# UNO-TH_Rev3e.net
KiCad netlist of a schematic drawn in Altium Designer
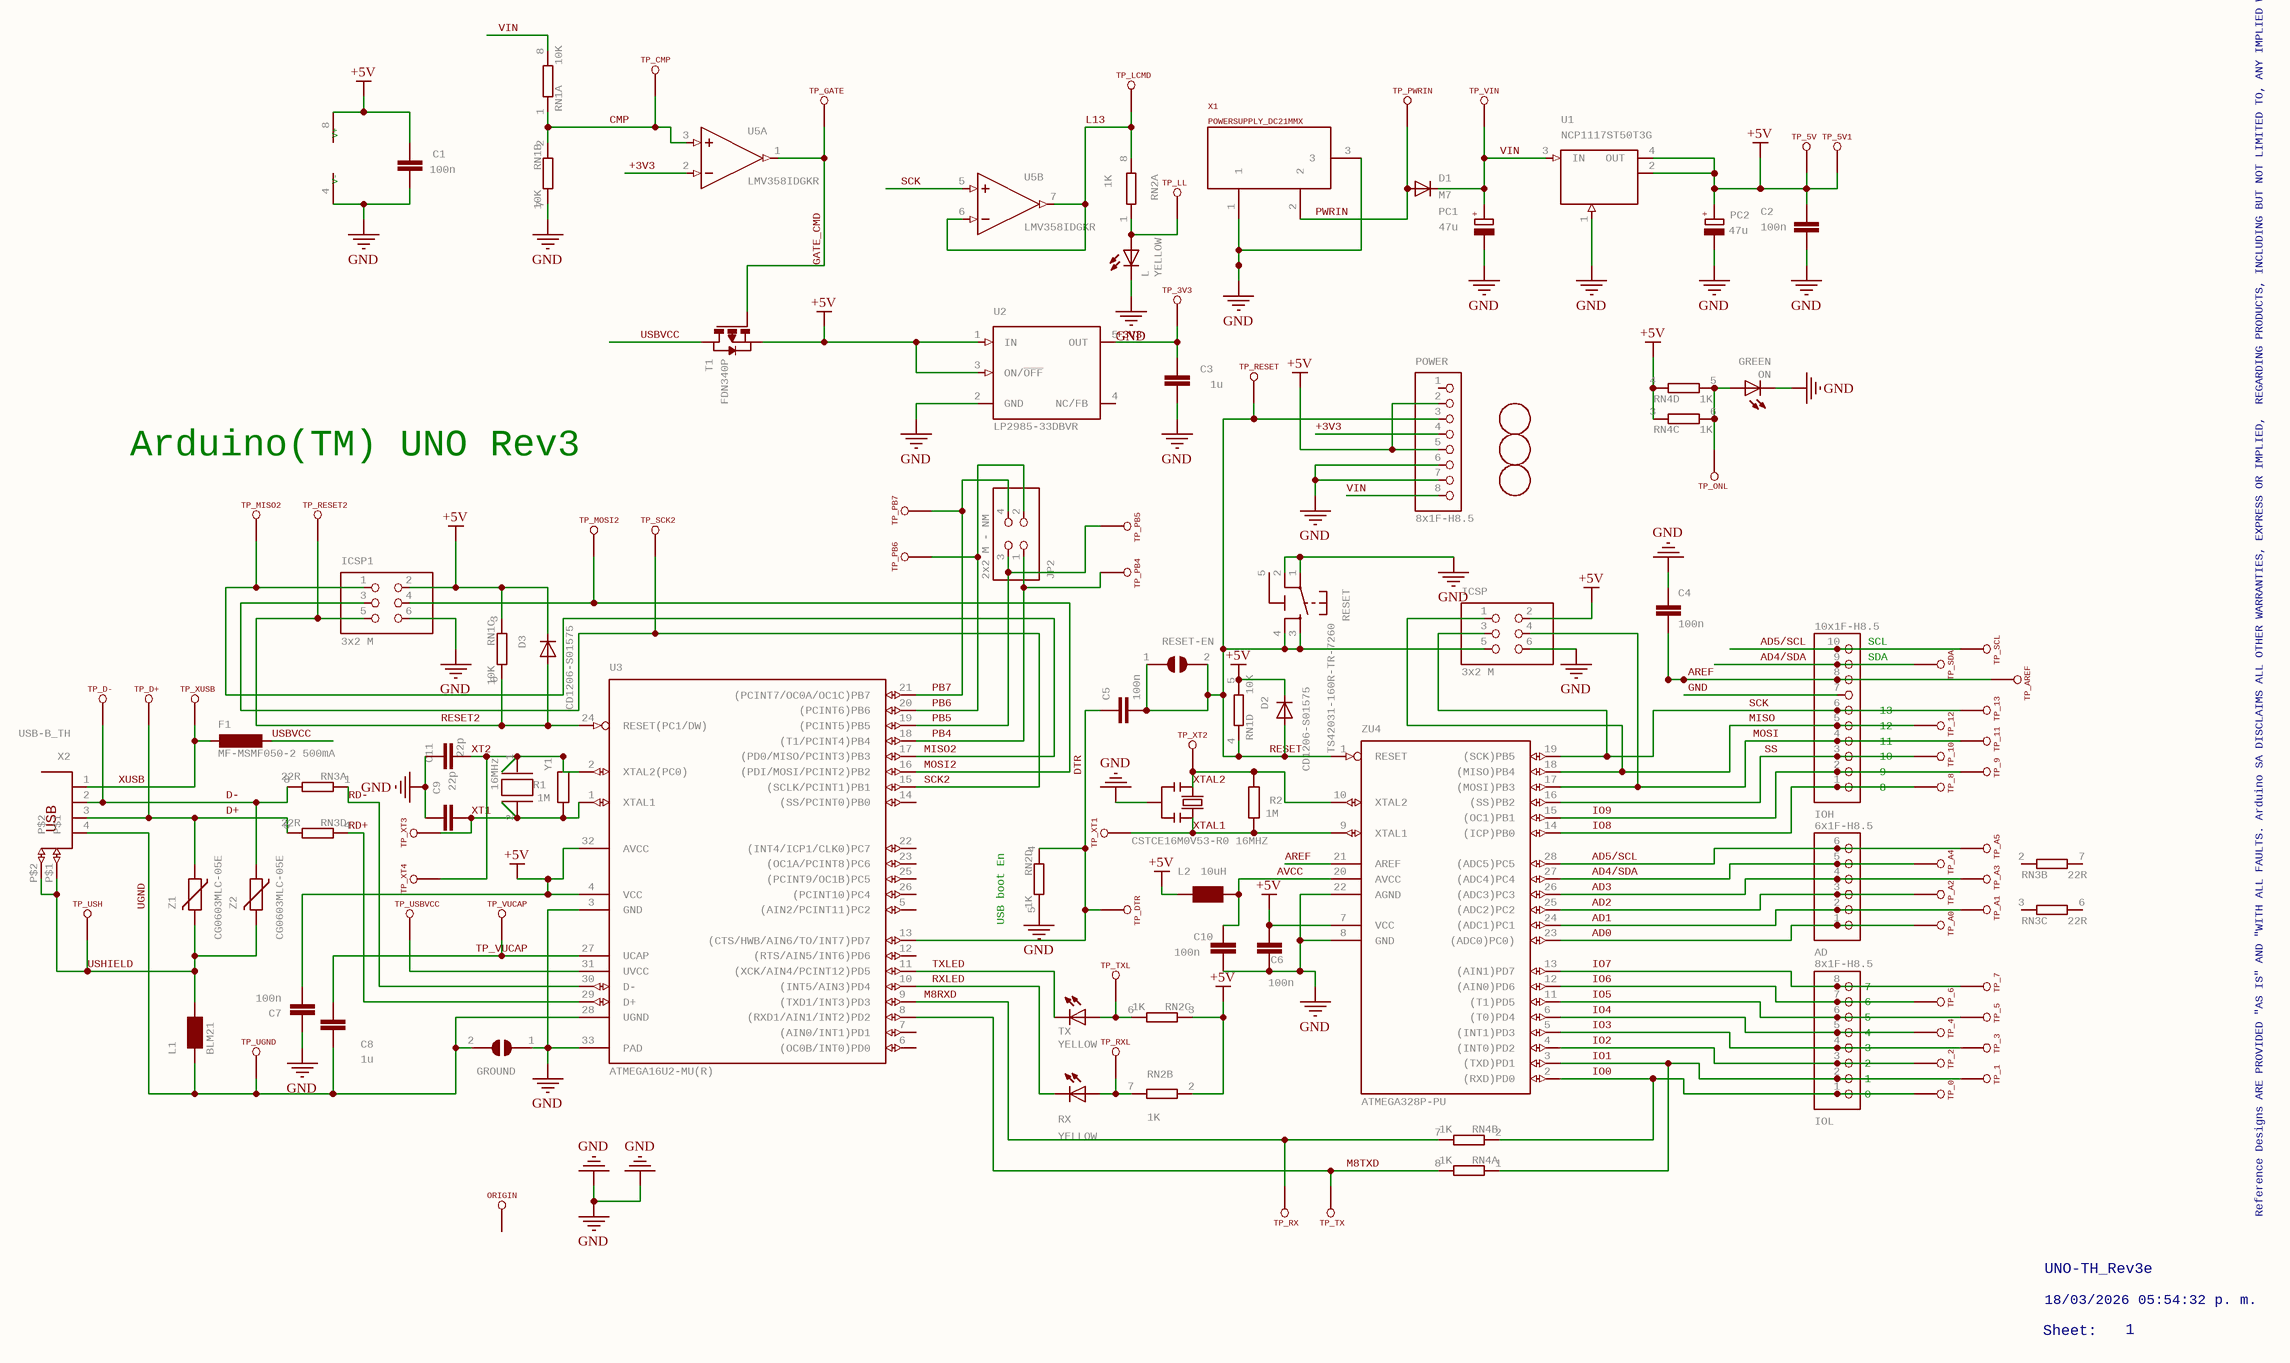
[diagram p0: UNO-TH_Rev3e.SchDoc]

(export (version "E")
  (design (tool "Eeschema 10.0.6"))
  (components
    (comp (ref "AD")
      (value "6x1F-H8.5")
      (footprint "1X06")
      (description "PIN HEADER")
      (libsource (lib "SmartPrj") (part "PINHD-1X6"))
    )
    (comp (ref "C1")
      (value "100n")
      (footprint "C0603-ROUND")
      (description "CAPACITOR, European symbol")
      (libsource (lib "") (part "C-EU0603-RND_1"))
    )
    (comp (ref "C2")
      (value "100n")
      (footprint "C0603-ROUND")
      (description "CAPACITOR, European symbol")
      (libsource (lib "SmartPrj") (part "C-EU0603-RND"))
    )
    (comp (ref "C3")
      (value "1u")
      (footprint "C0603-ROUND")
      (description "CAPACITOR, European symbol")
      (libsource (lib "") (part "C-EU0603-RND_1"))
    )
    (comp (ref "C4")
      (value "100n")
      (footprint "C0603-ROUND")
      (description "CAPACITOR, European symbol")
      (libsource (lib "") (part "C-EU0603-RND_2"))
    )
    (comp (ref "C5")
      (value "100n")
      (footprint "C0603-ROUND")
      (description "CAPACITOR, European symbol")
      (libsource (lib "") (part "C-EU0603-RND_1"))
    )
    (comp (ref "C6")
      (value "100n")
      (footprint "C0603-ROUND")
      (description "CAPACITOR, European symbol")
      (libsource (lib "SmartPrj") (part "C-EU0603-RND"))
    )
    (comp (ref "C7")
      (value "100n")
      (footprint "C0603-ROUND")
      (description "CAPACITOR, European symbol")
      (libsource (lib "") (part "C-EU0603-RND_3"))
    )
    (comp (ref "C8")
      (value "1u")
      (footprint "C0603-ROUND")
      (description "CAPACITOR, European symbol")
      (libsource (lib "") (part "C-EU0603-RND_3"))
    )
    (comp (ref "C9")
      (value "22p")
      (footprint "C0603-ROUND")
      (description "CAPACITOR, European symbol")
      (libsource (lib "") (part "C-EU0603-RND_2"))
    )
    (comp (ref "C10")
      (value "100n")
      (footprint "C0603-ROUND")
      (description "CAPACITOR, European symbol")
      (libsource (lib "SmartPrj") (part "C-EU0603-RND"))
    )
    (comp (ref "C11")
      (value "22p")
      (footprint "C0603-ROUND")
      (description "CAPACITOR, European symbol")
      (libsource (lib "") (part "C-EU0603-RND_2"))
    )
    (comp (ref "D1")
      (value "M7")
      (footprint "SMB")
      (description "DIODE")
      (libsource (lib "diode") (part "DIODE-SMB"))
    )
    (comp (ref "D2")
      (value "CD1206-S01575")
      (footprint "MINIMELF")
      (description "DIODE")
      (libsource (lib "diode") (part "DIODE-MINIMELF"))
    )
    (comp (ref "D3")
      (value "CD1206-S01575")
      (footprint "MINIMELF")
      (description "DIODE")
      (libsource (lib "diode") (part "DIODE-MINIMELF"))
    )
    (comp (ref "F1")
      (value "MF-MSMF050-2 500mA")
      (footprint "L1812")
      (description "INDUCTOR, European symbol")
      (libsource (lib "rcl") (part "L-EUL1812"))
    )
    (comp (ref "FD1")
      (value "FIDUCIALMOUNT")
      (footprint "FIDUCIA-MOUNT")
      (libsource (lib "SmartPrj") (part "FIDUCIALMOUNT"))
    )
    (comp (ref "FD2")
      (value "FIDUCIALMOUNT")
      (footprint "FIDUCIA-MOUNT")
      (libsource (lib "SmartPrj") (part "FIDUCIALMOUNT"))
    )
    (comp (ref "FD3")
      (value "FIDUCIALMOUNT")
      (footprint "FIDUCIA-MOUNT")
      (libsource (lib "SmartPrj") (part "FIDUCIALMOUNT"))
    )
    (comp (ref "GROUND")
      (value "SJ")
      (footprint "SJ")
      (description "SMD solder JUMPER")
      (libsource (lib "jumper") (part "SJ"))
    )
    (comp (ref "ICSP")
      (value "3x2 M")
      (footprint "2X03")
      (description "PIN HEADER")
      (libsource (lib "SmartPrj") (part "PINHD-2X3"))
    )
    (comp (ref "ICSP1")
      (value "3x2 M")
      (footprint "2X03")
      (description "PIN HEADER")
      (libsource (lib "SmartPrj") (part "PINHD-2X3"))
    )
    (comp (ref "IOH")
      (value "10x1F-H8.5")
      (footprint "1X10")
      (description "PIN HEADER")
      (libsource (lib "SmartPrj") (part "PINHD-1X10_ARD"))
    )
    (comp (ref "IOL")
      (value "8x1F-H8.5")
      (footprint "1X08")
      (description "PIN HEADER")
      (libsource (lib "SmartPrj") (part "PINHD-1X8"))
    )
    (comp (ref "JP2")
      (value "2x2 M - NM")
      (footprint "2X02")
      (description "PIN HEADER")
      (libsource (lib "SmartPrj") (part "PINHD-2X2"))
    )
    (comp (ref "L")
      (value "YELLOW")
      (footprint "CHIP-LED0805")
      (libsource (lib "led") (part "LEDCHIP-LED0805"))
    )
    (comp (ref "L1")
      (value "BLM21")
      (footprint "0805")
      (libsource (lib "wuerth-elektronik") (part "WE-CBF_0805"))
    )
    (comp (ref "L2")
      (value "10uH")
      (footprint "0805")
      (description "10uH 0805")
      (fields (field (name "PART_NUMBER") "CV201210-100K"))
      (libsource (lib "Induttanze") (part "0715_CV201210-100K"))
    )
    (comp (ref "ON")
      (value "GREEN")
      (footprint "CHIP-LED0805")
      (libsource (lib "led") (part "LEDCHIP-LED0805"))
    )
    (comp (ref "ORIGIN") (value "TP_SP") (footprint "TP-SP") (libsource (lib "SmartPrj") (part "TP_SP")))
    (comp (ref "PC1")
      (value "47u")
      (footprint "PANASONIC_D")
      (description "POLARIZED CAPACITOR, European symbol")
      (fields (field (name "+") "+"))
      (libsource (lib "rcl") (part "CPOL-EUD"))
    )
    (comp (ref "PC2")
      (value "47u")
      (footprint "PANASONIC_D")
      (description "POLARIZED CAPACITOR, European symbol")
      (fields (field (name "+") "+"))
      (libsource (lib "rcl") (part "CPOL-EUD"))
    )
    (comp (ref "POWER")
      (value "8x1F-H8.5")
      (footprint "1X08")
      (description "PIN HEADER")
      (libsource (lib "SmartPrj") (part "PINHD-1X8"))
    )
    (comp (ref "R1")
      (value "1M")
      (footprint "R0603-ROUND")
      (description "RESISTOR, European symbol")
      (libsource (lib "SmartPrj") (part "R-EU_R0603"))
    )
    (comp (ref "R2")
      (value "1M")
      (footprint "R0603-ROUND")
      (description "RESISTOR, European symbol")
      (libsource (lib "SmartPrj") (part "R-EU_R0603"))
    )
    (comp (ref "RESET")
      (value "TS42031-160R-TR-7260")
      (footprint "TS42")
      (description "TS42 Dongnan Electronics Tact switch VDC 12V - 50mA")
      (libsource (lib "SmartPrj") (part "TS42"))
    )
    (comp (ref "RESET-EN")
      (value "SJ")
      (footprint "SJ")
      (description "SMD solder JUMPER")
      (libsource (lib "jumper") (part "SJ"))
    )
    (comp (ref "RN1")
      (value "10K")
      (footprint "CAY16")
      (description "Array Chip Resistor   Source: RS Component / Phycomp")
      (libsource (lib "resistor-dil") (part "4R-NCAY16"))
    )
    (comp (ref "RN2")
      (value "1K")
      (footprint "CAY16")
      (description "Array Chip Resistor   Source: RS Component / Phycomp")
      (libsource (lib "resistor-dil") (part "4R-NCAY16"))
    )
    (comp (ref "RN3")
      (value "22R")
      (footprint "CAY16")
      (description "Array Chip Resistor   Source: RS Component / Phycomp")
      (libsource (lib "resistor-dil") (part "4R-NCAY16"))
    )
    (comp (ref "RN4")
      (value "1K")
      (footprint "CAY16")
      (description "Array Chip Resistor   Source: RS Component / Phycomp")
      (libsource (lib "resistor-dil") (part "4R-NCAY16"))
    )
    (comp (ref "RX")
      (value "YELLOW")
      (footprint "CHIP-LED0805")
      (libsource (lib "led") (part "LEDCHIP-LED0805"))
    )
    (comp (ref "T1")
      (value "FDN340P")
      (footprint "SOT-23")
      (description "MOS FET")
      (libsource (lib "zetex") (part "PMOSSOT23"))
    )
    (comp (ref "TP_0") (value "TP_SP") (footprint "TP-SP") (libsource (lib "SmartPrj") (part "TP_SP")))
    (comp (ref "TP_1") (value "TP_SP") (footprint "TP-SP") (libsource (lib "SmartPrj") (part "TP_SP")))
    (comp (ref "TP_2") (value "TP_SP") (footprint "TP-SP") (libsource (lib "SmartPrj") (part "TP_SP")))
    (comp (ref "TP_3") (value "TP_SP") (footprint "TP-SP") (libsource (lib "SmartPrj") (part "TP_SP")))
    (comp (ref "TP_3V3") (value "TP_SP") (footprint "TP-SP") (libsource (lib "SmartPrj") (part "TP_SP")))
    (comp (ref "TP_4") (value "TP_SP") (footprint "TP-SP") (libsource (lib "SmartPrj") (part "TP_SP")))
    (comp (ref "TP_5") (value "TP_SP") (footprint "TP-SP") (libsource (lib "SmartPrj") (part "TP_SP")))
    (comp (ref "TP_5V") (value "TP_SP") (footprint "TP-SP") (libsource (lib "SmartPrj") (part "TP_SP")))
    (comp (ref "TP_5V1") (value "TP_SP") (footprint "TP-SP") (libsource (lib "SmartPrj") (part "TP_SP")))
    (comp (ref "TP_6") (value "TP_SP") (footprint "TP-SP") (libsource (lib "SmartPrj") (part "TP_SP")))
    (comp (ref "TP_7") (value "TP_SP") (footprint "TP-SP") (libsource (lib "SmartPrj") (part "TP_SP")))
    (comp (ref "TP_8") (value "TP_SP") (footprint "TP-SP") (libsource (lib "SmartPrj") (part "TP_SP")))
    (comp (ref "TP_9") (value "TP_SP") (footprint "TP-SP") (libsource (lib "SmartPrj") (part "TP_SP")))
    (comp (ref "TP_10") (value "TP_SP") (footprint "TP-SP") (libsource (lib "SmartPrj") (part "TP_SP")))
    (comp (ref "TP_11") (value "TP_SP") (footprint "TP-SP") (libsource (lib "SmartPrj") (part "TP_SP")))
    (comp (ref "TP_12") (value "TP_SP") (footprint "TP-SP") (libsource (lib "SmartPrj") (part "TP_SP")))
    (comp (ref "TP_13") (value "TP_SP") (footprint "TP-SP") (libsource (lib "SmartPrj") (part "TP_SP")))
    (comp (ref "TP_A0") (value "TP_SP") (footprint "TP-SP") (libsource (lib "SmartPrj") (part "TP_SP")))
    (comp (ref "TP_A1") (value "TP_SP") (footprint "TP-SP") (libsource (lib "SmartPrj") (part "TP_SP")))
    (comp (ref "TP_A2") (value "TP_SP") (footprint "TP-SP") (libsource (lib "SmartPrj") (part "TP_SP")))
    (comp (ref "TP_A3") (value "TP_SP") (footprint "TP-SP") (libsource (lib "SmartPrj") (part "TP_SP")))
    (comp (ref "TP_A4") (value "TP_SP") (footprint "TP-SP") (libsource (lib "SmartPrj") (part "TP_SP")))
    (comp (ref "TP_A5") (value "TP_SP") (footprint "TP-SP") (libsource (lib "SmartPrj") (part "TP_SP")))
    (comp (ref "TP_AREF") (value "TP_SP") (footprint "TP-SP") (libsource (lib "SmartPrj") (part "TP_SP")))
    (comp (ref "TP_CMP") (value "TP_SP") (footprint "TP-SP") (libsource (lib "SmartPrj") (part "TP_SP")))
    (comp (ref "TP_D+") (value "TP_SP") (footprint "TP-SP") (libsource (lib "SmartPrj") (part "TP_SP")))
    (comp (ref "TP_D-") (value "TP_SP") (footprint "TP-SP") (libsource (lib "SmartPrj") (part "TP_SP")))
    (comp (ref "TP_DTR") (value "TP_SP") (footprint "TP-SP") (libsource (lib "SmartPrj") (part "TP_SP")))
    (comp (ref "TP_GATE") (value "TP_SP") (footprint "TP-SP") (libsource (lib "SmartPrj") (part "TP_SP")))
    (comp (ref "TP_LCMD") (value "TP_SP") (footprint "TP-SP") (libsource (lib "SmartPrj") (part "TP_SP")))
    (comp (ref "TP_LL") (value "TP_SP") (footprint "TP-SP") (libsource (lib "SmartPrj") (part "TP_SP")))
    (comp (ref "TP_MISO2") (value "TP_SP") (footprint "TP-SP") (libsource (lib "SmartPrj") (part "TP_SP")))
    (comp (ref "TP_MOSI2") (value "TP_SP") (footprint "TP-SP") (libsource (lib "SmartPrj") (part "TP_SP")))
    (comp (ref "TP_ONL") (value "TP_SP") (footprint "TP-SP") (libsource (lib "SmartPrj") (part "TP_SP")))
    (comp (ref "TP_PB4") (value "TP_SP") (footprint "TP-SP") (libsource (lib "SmartPrj") (part "TP_SP")))
    (comp (ref "TP_PB5") (value "TP_SP") (footprint "TP-SP") (libsource (lib "SmartPrj") (part "TP_SP")))
    (comp (ref "TP_PB6") (value "TP_SP") (footprint "TP-SP") (libsource (lib "SmartPrj") (part "TP_SP")))
    (comp (ref "TP_PB7") (value "TP_SP") (footprint "TP-SP") (libsource (lib "SmartPrj") (part "TP_SP")))
    (comp (ref "TP_PWRIN") (value "TP_SP") (footprint "TP-SP") (libsource (lib "SmartPrj") (part "TP_SP")))
    (comp (ref "TP_RESET") (value "TP_SP") (footprint "TP-SP") (libsource (lib "SmartPrj") (part "TP_SP")))
    (comp (ref "TP_RESET2") (value "TP_SP") (footprint "TP-SP") (libsource (lib "SmartPrj") (part "TP_SP")))
    (comp (ref "TP_RX") (value "TP_SP") (footprint "TP-SP") (libsource (lib "SmartPrj") (part "TP_SP")))
    (comp (ref "TP_RXL") (value "TP_SP") (footprint "TP-SP") (libsource (lib "SmartPrj") (part "TP_SP")))
    (comp (ref "TP_SCK2") (value "TP_SP") (footprint "TP-SP") (libsource (lib "SmartPrj") (part "TP_SP")))
    (comp (ref "TP_SCL") (value "TP_SP") (footprint "TP-SP") (libsource (lib "SmartPrj") (part "TP_SP")))
    (comp (ref "TP_SDA") (value "TP_SP") (footprint "TP-SP") (libsource (lib "SmartPrj") (part "TP_SP")))
    (comp (ref "TP_TX") (value "TP_SP") (footprint "TP-SP") (libsource (lib "SmartPrj") (part "TP_SP")))
    (comp (ref "TP_TXL") (value "TP_SP") (footprint "TP-SP") (libsource (lib "SmartPrj") (part "TP_SP")))
    (comp (ref "TP_UGND") (value "TP_SP") (footprint "TP-SP") (libsource (lib "SmartPrj") (part "TP_SP")))
    (comp (ref "TP_USBVCC") (value "TP_SP") (footprint "TP-SP") (libsource (lib "SmartPrj") (part "TP_SP")))
    (comp (ref "TP_USH") (value "TP_SP") (footprint "TP-SP") (libsource (lib "SmartPrj") (part "TP_SP")))
    (comp (ref "TP_VIN") (value "TP_SP") (footprint "TP-SP") (libsource (lib "SmartPrj") (part "TP_SP")))
    (comp (ref "TP_VUCAP") (value "TP_SP") (footprint "TP-SP") (libsource (lib "SmartPrj") (part "TP_SP")))
    (comp (ref "TP_XT1") (value "TP_SP") (footprint "TP-SP") (libsource (lib "SmartPrj") (part "TP_SP")))
    (comp (ref "TP_XT2") (value "TP_SP") (footprint "TP-SP") (libsource (lib "SmartPrj") (part "TP_SP")))
    (comp (ref "TP_XT3") (value "TP_SP") (footprint "TP-SP") (libsource (lib "SmartPrj") (part "TP_SP")))
    (comp (ref "TP_XT4") (value "TP_SP") (footprint "TP-SP") (libsource (lib "SmartPrj") (part "TP_SP")))
    (comp (ref "TP_XUSB") (value "TP_SP") (footprint "TP-SP") (libsource (lib "SmartPrj") (part "TP_SP")))
    (comp (ref "TX")
      (value "YELLOW")
      (footprint "CHIP-LED0805")
      (libsource (lib "led") (part "LEDCHIP-LED0805"))
    )
    (comp (ref "U1")
      (value "NCP1117ST50T3G")
      (footprint "SOT223")
      (libsource (lib "linear") (part "MC33269ST*"))
    )
    (comp (ref "U2")
      (value "LP2985-33DBVR")
      (footprint "SOT23-DBV")
      (libsource (lib "SmartPrj") (part "LP2985-XXDBVR"))
    )
    (comp (ref "U3")
      (value "ATMEGA16U2-MU(R)")
      (footprint "MLF32")
      (libsource (lib "SmartPrj") (part "ATMEGA16U2-MU"))
    )
    (comp (ref "U5")
      (value "LMV358IDGKR")
      (footprint "MSOP08")
      (fields (field (name "V+") "V+") (field (name "V-") "V-"))
      (libsource (lib "linear") (part "LMV358?*MM"))
    )
    (comp (ref "X1")
      (value "POWERSUPPLY_DC21MMX")
      (footprint "POWERSUPPLY_DC-21MM")
      (libsource (lib "SmartPrj") (part "POWERSUPPLY_DC21MMX"))
    )
    (comp (ref "X2")
      (value "USB-B_TH")
      (footprint "PN61729")
      (description "BERG USB connector")
      (fields (field (name "USB") "USB"))
      (libsource (lib "SmartPrj") (part "PN61729"))
    )
    (comp (ref "Y1")
      (value "16MHz")
      (footprint "QS")
      (description "CRYSTAL")
      (libsource (lib "SmartPrj") (part "XTAL/S"))
    )
    (comp (ref "Y2")
      (value "CSTCE16M0V53-R0 16MHZ")
      (footprint "RESONATOR")
      (libsource (lib "SmartPrj") (part "RESONATORMU"))
    )
    (comp (ref "Z1")
      (value "CG0603MLC-05E")
      (footprint "CT/CN0603")
      (description "VARISTOR")
      (libsource (lib "varistor") (part "VARISTORCN0603"))
    )
    (comp (ref "Z2")
      (value "CG0603MLC-05E")
      (footprint "CT/CN0603")
      (description "VARISTOR")
      (libsource (lib "varistor") (part "VARISTORCN0603"))
    )
    (comp (ref "ZU4")
      (value "ATMEGA328P-PU")
      (footprint "DIL28-3")
      (description "MICROCONTROLLER   4 Kbytes FLASH   128 bytes SRAM   256 bytes EEPROM   UART   6-channel 10 bit ADC")
      (libsource (lib "SmartPrj") (part "ATMEGA328P-PU"))
    )
  )
  (nets
    (net (code "1") (name "+5V") (class "Default")
      (node (ref "C1") (pin "2") (pinfunction "2_2") (pintype "passive"))
      (node (ref "C2") (pin "2") (pinfunction "2_2") (pintype "passive"))
      (node (ref "C6") (pin "2") (pinfunction "2_2") (pintype "passive"))
      (node (ref "C7") (pin "1") (pinfunction "1_1") (pintype "passive"))
      (node (ref "D2") (pin "C") (pinfunction "C_C") (pintype "passive"))
      (node (ref "D3") (pin "C") (pinfunction "C_C") (pintype "passive"))
      (node (ref "ICSP") (pin "2") (pinfunction "2_2") (pintype "passive"))
      (node (ref "ICSP1") (pin "2") (pinfunction "2_2") (pintype "passive"))
      (node (ref "L2") (pin "1") (pinfunction "1_1") (pintype "passive"))
      (node (ref "PC2") (pin "+") (pinfunction "+_+") (pintype "passive"))
      (node (ref "POWER") (pin "2") (pinfunction "2_2") (pintype "passive"))
      (node (ref "POWER") (pin "5") (pinfunction "5_5") (pintype "passive"))
      (node (ref "RN1") (pin "3") (pinfunction "1_3") (pintype "passive"))
      (node (ref "RN1") (pin "5") (pinfunction "2_5") (pintype "passive"))
      (node (ref "RN2") (pin "2") (pinfunction "1_2") (pintype "passive"))
      (node (ref "RN2") (pin "3") (pinfunction "1_3") (pintype "passive"))
      (node (ref "RN4") (pin "3") (pinfunction "1_3") (pintype "passive"))
      (node (ref "RN4") (pin "4") (pinfunction "1_4") (pintype "passive"))
      (node (ref "T1") (pin "2") (pinfunction "S_2") (pintype "passive"))
      (node (ref "TP_5V") (pin "X") (pinfunction "TESTP_X") (pintype "passive"))
      (node (ref "TP_5V1") (pin "X") (pinfunction "TESTP_X") (pintype "passive"))
      (node (ref "U1") (pin "2") (pinfunction "OUT_2") (pintype "passive"))
      (node (ref "U1") (pin "4") (pinfunction "OUT_4") (pintype "passive"))
      (node (ref "U2") (pin "1") (pinfunction "IN_1") (pintype "input"))
      (node (ref "U2") (pin "3") (pinfunction "ON/~{OFF}_3") (pintype "input"))
      (node (ref "U3") (pin "32") (pinfunction "AVCC_32") (pintype "power_in"))
      (node (ref "U3") (pin "4") (pinfunction "VCC_4") (pintype "power_in"))
      (node (ref "U5") (pin "8") (pinfunction "V+_8") (pintype "power_in"))
      (node (ref "ZU4") (pin "7") (pinfunction "VCC_7") (pintype "power_in"))
    )
    (net (code "2") (name "/+3V3") (class "Default")
      (node (ref "C3") (pin "2") (pinfunction "2_2") (pintype "passive"))
      (node (ref "POWER") (pin "4") (pinfunction "4_4") (pintype "passive"))
      (node (ref "TP_3V3") (pin "X") (pinfunction "TESTP_X") (pintype "passive"))
      (node (ref "U2") (pin "5") (pinfunction "OUT_5") (pintype "passive"))
      (node (ref "U5") (pin "2") (pinfunction "-IN_2") (pintype "input"))
    )
    (net (code "3") (name "/AD0") (class "Default")
      (node (ref "AD") (pin "1") (pinfunction "1_1") (pintype "passive"))
      (node (ref "TP_A0") (pin "X") (pinfunction "TESTP_X") (pintype "passive"))
      (node (ref "ZU4") (pin "23") (pinfunction "(ADC0)PC0)_23") (pintype "bidirectional"))
    )
    (net (code "4") (name "/AD1") (class "Default")
      (node (ref "AD") (pin "2") (pinfunction "2_2") (pintype "passive"))
      (node (ref "TP_A1") (pin "X") (pinfunction "TESTP_X") (pintype "passive"))
      (node (ref "ZU4") (pin "24") (pinfunction "(ADC1)PC1_24") (pintype "bidirectional"))
    )
    (net (code "5") (name "/AD2") (class "Default")
      (node (ref "AD") (pin "3") (pinfunction "3_3") (pintype "passive"))
      (node (ref "TP_A2") (pin "X") (pinfunction "TESTP_X") (pintype "passive"))
      (node (ref "ZU4") (pin "25") (pinfunction "(ADC2)PC2_25") (pintype "bidirectional"))
    )
    (net (code "6") (name "/AD3") (class "Default")
      (node (ref "AD") (pin "4") (pinfunction "4_4") (pintype "passive"))
      (node (ref "TP_A3") (pin "X") (pinfunction "TESTP_X") (pintype "passive"))
      (node (ref "ZU4") (pin "26") (pinfunction "(ADC3)PC3_26") (pintype "bidirectional"))
    )
    (net (code "7") (name "/AD4{slash}SDA") (class "Default")
      (node (ref "AD") (pin "5") (pinfunction "5_5") (pintype "passive"))
      (node (ref "IOH") (pin "9") (pinfunction "9_9") (pintype "passive"))
      (node (ref "TP_A4") (pin "X") (pinfunction "TESTP_X") (pintype "passive"))
      (node (ref "TP_SDA") (pin "X") (pinfunction "TESTP_X") (pintype "passive"))
      (node (ref "ZU4") (pin "27") (pinfunction "(ADC4)PC4_27") (pintype "bidirectional"))
    )
    (net (code "8") (name "/AD5{slash}SCL") (class "Default")
      (node (ref "AD") (pin "6") (pinfunction "6_6") (pintype "passive"))
      (node (ref "IOH") (pin "10") (pinfunction "10_10") (pintype "passive"))
      (node (ref "TP_A5") (pin "X") (pinfunction "TESTP_X") (pintype "passive"))
      (node (ref "TP_SCL") (pin "X") (pinfunction "TESTP_X") (pintype "passive"))
      (node (ref "ZU4") (pin "28") (pinfunction "(ADC5)PC5_28") (pintype "bidirectional"))
    )
    (net (code "9") (name "/AREF") (class "Default")
      (node (ref "C4") (pin "2") (pinfunction "2_2") (pintype "passive"))
      (node (ref "IOH") (pin "8") (pinfunction "8_8") (pintype "passive"))
      (node (ref "TP_AREF") (pin "X") (pinfunction "TESTP_X") (pintype "passive"))
      (node (ref "ZU4") (pin "21") (pinfunction "AREF_21") (pintype "passive"))
    )
    (net (code "10") (name "/AVCC") (class "Default")
      (node (ref "C10") (pin "2") (pinfunction "2_2") (pintype "passive"))
      (node (ref "L2") (pin "2") (pinfunction "2_2") (pintype "passive"))
      (node (ref "ZU4") (pin "20") (pinfunction "AVCC_20") (pintype "power_in"))
    )
    (net (code "11") (name "/CMP") (class "Default")
      (node (ref "RN1") (pin "1") (pinfunction "1_1") (pintype "passive"))
      (node (ref "RN1") (pin "2") (pinfunction "1_2") (pintype "passive"))
      (node (ref "TP_CMP") (pin "X") (pinfunction "TESTP_X") (pintype "passive"))
      (node (ref "U5") (pin "3") (pinfunction "+IN_3") (pintype "input"))
    )
    (net (code "12") (name "/D+") (class "Default")
      (node (ref "RN3") (pin "5") (pinfunction "2_5") (pintype "passive"))
      (node (ref "TP_D+") (pin "X") (pinfunction "TESTP_X") (pintype "passive"))
      (node (ref "X2") (pin "3") (pinfunction "3_3") (pintype "bidirectional"))
      (node (ref "Z1") (pin "1") (pinfunction "1_1") (pintype "passive"))
    )
    (net (code "13") (name "/D-") (class "Default")
      (node (ref "RN3") (pin "8") (pinfunction "2_8") (pintype "passive"))
      (node (ref "TP_D-") (pin "X") (pinfunction "TESTP_X") (pintype "passive"))
      (node (ref "X2") (pin "2") (pinfunction "2_2") (pintype "bidirectional"))
      (node (ref "Z2") (pin "1") (pinfunction "1_1") (pintype "passive"))
    )
    (net (code "14") (name "/DTR") (class "Default")
      (node (ref "C5") (pin "1") (pinfunction "1_1") (pintype "passive"))
      (node (ref "RN2") (pin "4") (pinfunction "1_4") (pintype "passive"))
      (node (ref "TP_DTR") (pin "X") (pinfunction "TESTP_X") (pintype "passive"))
      (node (ref "U3") (pin "13") (pinfunction "(CTS/HWB/AIN6/TO/INT7)PD7_13") (pintype "bidirectional"))
    )
    (net (code "15") (name "/GATE_CMD") (class "Default")
      (node (ref "T1") (pin "3") (pinfunction "G_3") (pintype "passive"))
      (node (ref "TP_GATE") (pin "X") (pinfunction "TESTP_X") (pintype "passive"))
      (node (ref "U5") (pin "1") (pinfunction "OUT_1") (pintype "output"))
    )
    (net (code "16") (name "/IO0") (class "Default")
      (node (ref "IOL") (pin "1") (pinfunction "1_1") (pintype "passive"))
      (node (ref "RN4") (pin "2") (pinfunction "1_2") (pintype "passive"))
      (node (ref "TP_0") (pin "X") (pinfunction "TESTP_X") (pintype "passive"))
      (node (ref "ZU4") (pin "2") (pinfunction "(RXD)PD0_2") (pintype "bidirectional"))
    )
    (net (code "17") (name "/IO1") (class "Default")
      (node (ref "IOL") (pin "2") (pinfunction "2_2") (pintype "passive"))
      (node (ref "RN4") (pin "1") (pinfunction "1_1") (pintype "passive"))
      (node (ref "TP_1") (pin "X") (pinfunction "TESTP_X") (pintype "passive"))
      (node (ref "ZU4") (pin "3") (pinfunction "(TXD)PD1_3") (pintype "bidirectional"))
    )
    (net (code "18") (name "/IO2") (class "Default")
      (node (ref "IOL") (pin "3") (pinfunction "3_3") (pintype "passive"))
      (node (ref "TP_2") (pin "X") (pinfunction "TESTP_X") (pintype "passive"))
      (node (ref "ZU4") (pin "4") (pinfunction "(INT0)PD2_4") (pintype "bidirectional"))
    )
    (net (code "19") (name "/IO3") (class "Default")
      (node (ref "IOL") (pin "4") (pinfunction "4_4") (pintype "passive"))
      (node (ref "TP_3") (pin "X") (pinfunction "TESTP_X") (pintype "passive"))
      (node (ref "ZU4") (pin "5") (pinfunction "(INT1)PD3_5") (pintype "bidirectional"))
    )
    (net (code "20") (name "/IO4") (class "Default")
      (node (ref "IOL") (pin "5") (pinfunction "5_5") (pintype "passive"))
      (node (ref "TP_4") (pin "X") (pinfunction "TESTP_X") (pintype "passive"))
      (node (ref "ZU4") (pin "6") (pinfunction "(T0)PD4_6") (pintype "bidirectional"))
    )
    (net (code "21") (name "/IO5") (class "Default")
      (node (ref "IOL") (pin "6") (pinfunction "6_6") (pintype "passive"))
      (node (ref "TP_5") (pin "X") (pinfunction "TESTP_X") (pintype "passive"))
      (node (ref "ZU4") (pin "11") (pinfunction "(T1)PD5_11") (pintype "bidirectional"))
    )
    (net (code "22") (name "/IO6") (class "Default")
      (node (ref "IOL") (pin "7") (pinfunction "7_7") (pintype "passive"))
      (node (ref "TP_6") (pin "X") (pinfunction "TESTP_X") (pintype "passive"))
      (node (ref "ZU4") (pin "12") (pinfunction "(AIN0)PD6_12") (pintype "bidirectional"))
    )
    (net (code "23") (name "/IO7") (class "Default")
      (node (ref "IOL") (pin "8") (pinfunction "8_8") (pintype "passive"))
      (node (ref "TP_7") (pin "X") (pinfunction "TESTP_X") (pintype "passive"))
      (node (ref "ZU4") (pin "13") (pinfunction "(AIN1)PD7_13") (pintype "bidirectional"))
    )
    (net (code "24") (name "/IO8") (class "Default")
      (node (ref "IOH") (pin "1") (pinfunction "1_1") (pintype "passive"))
      (node (ref "TP_8") (pin "X") (pinfunction "TESTP_X") (pintype "passive"))
      (node (ref "ZU4") (pin "14") (pinfunction "(ICP)PB0_14") (pintype "bidirectional"))
    )
    (net (code "25") (name "/IO9") (class "Default")
      (node (ref "IOH") (pin "2") (pinfunction "2_2") (pintype "passive"))
      (node (ref "TP_9") (pin "X") (pinfunction "TESTP_X") (pintype "passive"))
      (node (ref "ZU4") (pin "15") (pinfunction "(OC1)PB1_15") (pintype "bidirectional"))
    )
    (net (code "26") (name "/L13") (class "Default")
      (node (ref "RN2") (pin "8") (pinfunction "2_8") (pintype "passive"))
      (node (ref "TP_LCMD") (pin "X") (pinfunction "TESTP_X") (pintype "passive"))
      (node (ref "U5") (pin "6") (pinfunction "-IN_6") (pintype "input"))
      (node (ref "U5") (pin "7") (pinfunction "OUT_7") (pintype "output"))
    )
    (net (code "27") (name "/M8RXD") (class "Default")
      (node (ref "RN4") (pin "7") (pinfunction "2_7") (pintype "passive"))
      (node (ref "TP_RX") (pin "X") (pinfunction "TESTP_X") (pintype "passive"))
      (node (ref "U3") (pin "9") (pinfunction "(TXD1/INT3)PD3_9") (pintype "bidirectional"))
    )
    (net (code "28") (name "/M8TXD") (class "Default")
      (node (ref "RN4") (pin "8") (pinfunction "2_8") (pintype "passive"))
      (node (ref "TP_TX") (pin "X") (pinfunction "TESTP_X") (pintype "passive"))
      (node (ref "U3") (pin "8") (pinfunction "(RXD1/AIN1/INT2)PD2_8") (pintype "bidirectional"))
    )
    (net (code "29") (name "/MISO") (class "Default")
      (node (ref "ICSP") (pin "1") (pinfunction "1_1") (pintype "passive"))
      (node (ref "IOH") (pin "5") (pinfunction "5_5") (pintype "passive"))
      (node (ref "TP_12") (pin "X") (pinfunction "TESTP_X") (pintype "passive"))
      (node (ref "ZU4") (pin "18") (pinfunction "(MISO)PB4_18") (pintype "bidirectional"))
    )
    (net (code "30") (name "/MISO2") (class "Default")
      (node (ref "ICSP1") (pin "1") (pinfunction "1_1") (pintype "passive"))
      (node (ref "TP_MISO2") (pin "X") (pinfunction "TESTP_X") (pintype "passive"))
      (node (ref "U3") (pin "17") (pinfunction "(PD0/MISO/PCINT3)PB3_17") (pintype "bidirectional"))
    )
    (net (code "31") (name "/MOSI") (class "Default")
      (node (ref "ICSP") (pin "4") (pinfunction "4_4") (pintype "passive"))
      (node (ref "IOH") (pin "4") (pinfunction "4_4") (pintype "passive"))
      (node (ref "TP_11") (pin "X") (pinfunction "TESTP_X") (pintype "passive"))
      (node (ref "ZU4") (pin "17") (pinfunction "(MOSI)PB3_17") (pintype "bidirectional"))
    )
    (net (code "32") (name "/MOSI2") (class "Default")
      (node (ref "ICSP1") (pin "4") (pinfunction "4_4") (pintype "passive"))
      (node (ref "TP_MOSI2") (pin "X") (pinfunction "TESTP_X") (pintype "passive"))
      (node (ref "U3") (pin "16") (pinfunction "(PDI/MOSI/PCINT2)PB2_16") (pintype "bidirectional"))
    )
    (net (code "33") (name "/PB4") (class "Default")
      (node (ref "JP2") (pin "1") (pinfunction "1_1") (pintype "passive"))
      (node (ref "TP_PB4") (pin "X") (pinfunction "TESTP_X") (pintype "passive"))
      (node (ref "U3") (pin "18") (pinfunction "(T1/PCINT4)PB4_18") (pintype "bidirectional"))
    )
    (net (code "34") (name "/PB5") (class "Default")
      (node (ref "JP2") (pin "3") (pinfunction "3_3") (pintype "passive"))
      (node (ref "TP_PB5") (pin "X") (pinfunction "TESTP_X") (pintype "passive"))
      (node (ref "U3") (pin "19") (pinfunction "(PCINT5)PB5_19") (pintype "bidirectional"))
    )
    (net (code "35") (name "/PB6") (class "Default")
      (node (ref "JP2") (pin "2") (pinfunction "2_2") (pintype "passive"))
      (node (ref "TP_PB6") (pin "X") (pinfunction "TESTP_X") (pintype "passive"))
      (node (ref "U3") (pin "20") (pinfunction "(PCINT6)PB6_20") (pintype "bidirectional"))
    )
    (net (code "36") (name "/PB7") (class "Default")
      (node (ref "JP2") (pin "4") (pinfunction "4_4") (pintype "passive"))
      (node (ref "TP_PB7") (pin "X") (pinfunction "TESTP_X") (pintype "passive"))
      (node (ref "U3") (pin "21") (pinfunction "(PCINT7/OC0A/OC1C)PB7_21") (pintype "bidirectional"))
    )
    (net (code "37") (name "/PWRIN") (class "Default")
      (node (ref "D1") (pin "A") (pinfunction "A_A") (pintype "passive"))
      (node (ref "TP_PWRIN") (pin "X") (pinfunction "TESTP_X") (pintype "passive"))
      (node (ref "X1") (pin "2") (pinfunction "2_2") (pintype "power_in"))
    )
    (net (code "38") (name "/RD+") (class "Default")
      (node (ref "RN3") (pin "4") (pinfunction "1_4") (pintype "passive"))
      (node (ref "U3") (pin "29") (pinfunction "D+_29") (pintype "bidirectional"))
    )
    (net (code "39") (name "/RD-") (class "Default")
      (node (ref "RN3") (pin "1") (pinfunction "1_1") (pintype "passive"))
      (node (ref "U3") (pin "30") (pinfunction "D-_30") (pintype "bidirectional"))
    )
    (net (code "40") (name "/RESET") (class "Default")
      (node (ref "C5") (pin "2") (pinfunction "2_2") (pintype "passive"))
      (node (ref "D2") (pin "A") (pinfunction "A_A") (pintype "passive"))
      (node (ref "ICSP") (pin "5") (pinfunction "5_5") (pintype "passive"))
      (node (ref "POWER") (pin "3") (pinfunction "3_3") (pintype "passive"))
      (node (ref "RESET") (pin "3") (pinfunction "3_3") (pintype "passive"))
      (node (ref "RESET") (pin "4") (pinfunction "4_4") (pintype "passive"))
      (node (ref "RESET-EN") (pin "1") (pinfunction "1_1") (pintype "passive"))
      (node (ref "RESET-EN") (pin "2") (pinfunction "2_2") (pintype "passive"))
      (node (ref "RN1") (pin "4") (pinfunction "1_4") (pintype "passive"))
      (node (ref "TP_RESET") (pin "X") (pinfunction "TESTP_X") (pintype "passive"))
      (node (ref "ZU4") (pin "1") (pinfunction "RESET_1") (pintype "input"))
    )
    (net (code "41") (name "/RESET2") (class "Default")
      (node (ref "D3") (pin "A") (pinfunction "A_A") (pintype "passive"))
      (node (ref "ICSP1") (pin "5") (pinfunction "5_5") (pintype "passive"))
      (node (ref "RN1") (pin "6") (pinfunction "2_6") (pintype "passive"))
      (node (ref "TP_RESET2") (pin "X") (pinfunction "TESTP_X") (pintype "passive"))
      (node (ref "U3") (pin "24") (pinfunction "RESET(PC1/DW)_24") (pintype "input"))
    )
    (net (code "42") (name "/RXLED") (class "Default")
      (node (ref "RX") (pin "C") (pinfunction "C_C") (pintype "passive"))
      (node (ref "U3") (pin "10") (pinfunction "(INT5/AIN3)PD4_10") (pintype "bidirectional"))
    )
    (net (code "43") (name "/SCK") (class "Default")
      (node (ref "ICSP") (pin "3") (pinfunction "3_3") (pintype "passive"))
      (node (ref "IOH") (pin "6") (pinfunction "6_6") (pintype "passive"))
      (node (ref "TP_13") (pin "X") (pinfunction "TESTP_X") (pintype "passive"))
      (node (ref "U5") (pin "5") (pinfunction "+IN_5") (pintype "input"))
      (node (ref "ZU4") (pin "19") (pinfunction "(SCK)PB5_19") (pintype "bidirectional"))
    )
    (net (code "44") (name "/SCK2") (class "Default")
      (node (ref "ICSP1") (pin "3") (pinfunction "3_3") (pintype "passive"))
      (node (ref "TP_SCK2") (pin "X") (pinfunction "TESTP_X") (pintype "passive"))
      (node (ref "U3") (pin "15") (pinfunction "(SCLK/PCINT1)PB1_15") (pintype "bidirectional"))
    )
    (net (code "45") (name "/SS") (class "Default")
      (node (ref "IOH") (pin "3") (pinfunction "3_3") (pintype "passive"))
      (node (ref "TP_10") (pin "X") (pinfunction "TESTP_X") (pintype "passive"))
      (node (ref "ZU4") (pin "16") (pinfunction "(SS)PB2_16") (pintype "bidirectional"))
    )
    (net (code "46") (name "/TP_VUCAP") (class "Default")
      (node (ref "C8") (pin "1") (pinfunction "1_1") (pintype "passive"))
      (node (ref "TP_VUCAP") (pin "X") (pinfunction "TESTP_X") (pintype "passive"))
      (node (ref "U3") (pin "27") (pinfunction "UCAP_27") (pintype "passive"))
    )
    (net (code "47") (name "/TXLED") (class "Default")
      (node (ref "TX") (pin "C") (pinfunction "C_C") (pintype "passive"))
      (node (ref "U3") (pin "11") (pinfunction "(XCK/AIN4/PCINT12)PD5_11") (pintype "bidirectional"))
    )
    (net (code "48") (name "/UGND") (class "Default")
      (node (ref "C8") (pin "2") (pinfunction "2_2") (pintype "passive"))
      (node (ref "GROUND") (pin "2") (pinfunction "2_2") (pintype "passive"))
      (node (ref "L1") (pin "1") (pinfunction "1_1") (pintype "passive"))
      (node (ref "TP_UGND") (pin "X") (pinfunction "TESTP_X") (pintype "passive"))
      (node (ref "U3") (pin "28") (pinfunction "UGND_28") (pintype "power_in"))
      (node (ref "X2") (pin "4") (pinfunction "4_4") (pintype "bidirectional"))
    )
    (net (code "49") (name "/USBVCC") (class "Default")
      (node (ref "F1") (pin "1") (pinfunction "1_1") (pintype "passive"))
      (node (ref "T1") (pin "1") (pinfunction "D_1") (pintype "passive"))
    )
    (net (code "50") (name "/USHIELD") (class "Default")
      (node (ref "L1") (pin "2") (pinfunction "2_2") (pintype "passive"))
      (node (ref "TP_USH") (pin "X") (pinfunction "TESTP_X") (pintype "passive"))
      (node (ref "X2") (pin "P$1") (pinfunction "P$1_P$1") (pintype "bidirectional"))
      (node (ref "X2") (pin "P$2") (pinfunction "P$2_P$2") (pintype "bidirectional"))
      (node (ref "Z1") (pin "2") (pinfunction "2_2") (pintype "passive"))
      (node (ref "Z2") (pin "2") (pinfunction "2_2") (pintype "passive"))
    )
    (net (code "51") (name "/VIN") (class "Default")
      (node (ref "D1") (pin "C") (pinfunction "C_C") (pintype "passive"))
      (node (ref "PC1") (pin "+") (pinfunction "+_+") (pintype "passive"))
      (node (ref "POWER") (pin "8") (pinfunction "8_8") (pintype "passive"))
      (node (ref "RN1") (pin "8") (pinfunction "2_8") (pintype "passive"))
      (node (ref "TP_VIN") (pin "X") (pinfunction "TESTP_X") (pintype "passive"))
      (node (ref "U1") (pin "3") (pinfunction "IN_3") (pintype "input"))
    )
    (net (code "52") (name "/XT1") (class "Default")
      (node (ref "C9") (pin "1") (pinfunction "1_1") (pintype "passive"))
      (node (ref "R1") (pin "1") (pinfunction "1_1") (pintype "passive"))
      (node (ref "TP_XT3") (pin "X") (pinfunction "TESTP_X") (pintype "passive"))
      (node (ref "U3") (pin "1") (pinfunction "XTAL1_1") (pintype "bidirectional"))
      (node (ref "Y1") (pin "2") (pinfunction "2_2") (pintype "passive"))
    )
    (net (code "53") (name "/XT2") (class "Default")
      (node (ref "C11") (pin "1") (pinfunction "1_1") (pintype "passive"))
      (node (ref "R1") (pin "2") (pinfunction "2_2") (pintype "passive"))
      (node (ref "TP_XT4") (pin "X") (pinfunction "TESTP_X") (pintype "passive"))
      (node (ref "U3") (pin "2") (pinfunction "XTAL2(PC0)_2") (pintype "bidirectional"))
      (node (ref "Y1") (pin "1") (pinfunction "1_1") (pintype "passive"))
    )
    (net (code "54") (name "/XTAL1") (class "Default")
      (node (ref "R2") (pin "1") (pinfunction "1_1") (pintype "passive"))
      (node (ref "TP_XT1") (pin "X") (pinfunction "TESTP_X") (pintype "passive"))
      (node (ref "Y2") (pin "3") (pinfunction "3_3") (pintype "passive"))
      (node (ref "ZU4") (pin "9") (pinfunction "XTAL1_9") (pintype "bidirectional"))
    )
    (net (code "55") (name "/XTAL2") (class "Default")
      (node (ref "R2") (pin "2") (pinfunction "2_2") (pintype "passive"))
      (node (ref "TP_XT2") (pin "X") (pinfunction "TESTP_X") (pintype "passive"))
      (node (ref "Y2") (pin "1") (pinfunction "1_1") (pintype "passive"))
      (node (ref "ZU4") (pin "10") (pinfunction "XTAL2_10") (pintype "bidirectional"))
    )
    (net (code "56") (name "/XUSB") (class "Default")
      (node (ref "F1") (pin "2") (pinfunction "2_2") (pintype "passive"))
      (node (ref "TP_XUSB") (pin "X") (pinfunction "TESTP_X") (pintype "passive"))
      (node (ref "X2") (pin "1") (pinfunction "1_1") (pintype "bidirectional"))
    )
    (net (code "57") (name "GND") (class "Default")
      (node (ref "C1") (pin "1") (pinfunction "1_1") (pintype "passive"))
      (node (ref "C10") (pin "1") (pinfunction "1_1") (pintype "passive"))
      (node (ref "C11") (pin "2") (pinfunction "2_2") (pintype "passive"))
      (node (ref "C2") (pin "1") (pinfunction "1_1") (pintype "passive"))
      (node (ref "C3") (pin "1") (pinfunction "1_1") (pintype "passive"))
      (node (ref "C4") (pin "1") (pinfunction "1_1") (pintype "passive"))
      (node (ref "C6") (pin "1") (pinfunction "1_1") (pintype "passive"))
      (node (ref "C7") (pin "2") (pinfunction "2_2") (pintype "passive"))
      (node (ref "C9") (pin "2") (pinfunction "2_2") (pintype "passive"))
      (node (ref "GROUND") (pin "1") (pinfunction "1_1") (pintype "passive"))
      (node (ref "ICSP") (pin "6") (pinfunction "6_6") (pintype "passive"))
      (node (ref "ICSP1") (pin "6") (pinfunction "6_6") (pintype "passive"))
      (node (ref "IOH") (pin "7") (pinfunction "7_7") (pintype "passive"))
      (node (ref "L") (pin "C") (pinfunction "C_C") (pintype "passive"))
      (node (ref "ON") (pin "C") (pinfunction "C_C") (pintype "passive"))
      (node (ref "PC1") (pin "-") (pinfunction "-_-") (pintype "passive"))
      (node (ref "PC2") (pin "-") (pinfunction "-_-") (pintype "passive"))
      (node (ref "POWER") (pin "6") (pinfunction "6_6") (pintype "passive"))
      (node (ref "POWER") (pin "7") (pinfunction "7_7") (pintype "passive"))
      (node (ref "RESET") (pin "1") (pinfunction "1_1") (pintype "passive"))
      (node (ref "RESET") (pin "2") (pinfunction "2_2") (pintype "passive"))
      (node (ref "RN1") (pin "7") (pinfunction "2_7") (pintype "passive"))
      (node (ref "RN2") (pin "5") (pinfunction "2_5") (pintype "passive"))
      (node (ref "U1") (pin "1") (pinfunction "GND/ADJ_1") (pintype "input"))
      (node (ref "U2") (pin "2") (pinfunction "GND_2") (pintype "power_in"))
      (node (ref "U3") (pin "3") (pinfunction "GND_3") (pintype "power_in"))
      (node (ref "U3") (pin "33") (pinfunction "PAD_33") (pintype "power_in"))
      (node (ref "U5") (pin "4") (pinfunction "V-_4") (pintype "power_in"))
      (node (ref "X1") (pin "1") (pinfunction "1_1") (pintype "power_in"))
      (node (ref "X1") (pin "3") (pinfunction "3_3") (pintype "power_in"))
      (node (ref "Y2") (pin "2") (pinfunction "2_2") (pintype "passive"))
      (node (ref "ZU4") (pin "22") (pinfunction "AGND_22") (pintype "power_in"))
      (node (ref "ZU4") (pin "8") (pinfunction "GND_8") (pintype "power_in"))
    )
    (net (code "58") (name "Net-(RN2B-2)") (class "Default")
      (node (ref "RN2") (pin "7") (pinfunction "2_7") (pintype "passive"))
      (node (ref "RX") (pin "A") (pinfunction "A_A") (pintype "passive"))
      (node (ref "TP_RXL") (pin "X") (pinfunction "TESTP_X") (pintype "passive"))
    )
    (net (code "59") (name "Net-(RN2C-2)") (class "Default")
      (node (ref "RN2") (pin "6") (pinfunction "2_6") (pintype "passive"))
      (node (ref "TP_TXL") (pin "X") (pinfunction "TESTP_X") (pintype "passive"))
      (node (ref "TX") (pin "A") (pinfunction "A_A") (pintype "passive"))
    )
    (net (code "60") (name "Net-(RN4C-2)") (class "Default")
      (node (ref "ON") (pin "A") (pinfunction "A_A") (pintype "passive"))
      (node (ref "RN4") (pin "5") (pinfunction "2_5") (pintype "passive"))
      (node (ref "RN4") (pin "6") (pinfunction "2_6") (pintype "passive"))
      (node (ref "TP_ONL") (pin "X") (pinfunction "TESTP_X") (pintype "passive"))
    )
    (net (code "61") (name "Net-(TP_LL-TESTP)") (class "Default")
      (node (ref "L") (pin "A") (pinfunction "A_A") (pintype "passive"))
      (node (ref "RN2") (pin "1") (pinfunction "1_1") (pintype "passive"))
      (node (ref "TP_LL") (pin "X") (pinfunction "TESTP_X") (pintype "passive"))
    )
    (net (code "62") (name "Net-(TP_USBVCC-TESTP)") (class "Default")
      (node (ref "TP_USBVCC") (pin "X") (pinfunction "TESTP_X") (pintype "passive"))
      (node (ref "U3") (pin "31") (pinfunction "UVCC_31") (pintype "power_in"))
    )
    (net (code "63") (name "unconnected-(ORIGIN-TESTP-PadX)") (class "Default")
      (node (ref "ORIGIN") (pin "X") (pinfunction "TESTP_X") (pintype "passive"))
    )
    (net (code "64") (name "unconnected-(POWER-Pad1)") (class "Default")
      (node (ref "POWER") (pin "1") (pinfunction "1_1") (pintype "passive"))
    )
    (net (code "65") (name "unconnected-(RESET-5-GND-Pad5)") (class "Default")
      (node (ref "RESET") (pin "5") (pinfunction "5-GND_5") (pintype "power_in"))
    )
    (net (code "66") (name "unconnected-(RN3B-1-Pad2)") (class "Default")
      (node (ref "RN3") (pin "2") (pinfunction "1_2") (pintype "passive"))
    )
    (net (code "67") (name "unconnected-(RN3B-2-Pad7)") (class "Default")
      (node (ref "RN3") (pin "7") (pinfunction "2_7") (pintype "passive"))
    )
    (net (code "68") (name "unconnected-(RN3C-1-Pad3)") (class "Default")
      (node (ref "RN3") (pin "3") (pinfunction "1_3") (pintype "passive"))
    )
    (net (code "69") (name "unconnected-(RN3C-2-Pad6)") (class "Default")
      (node (ref "RN3") (pin "6") (pinfunction "2_6") (pintype "passive"))
    )
    (net (code "70") (name "unconnected-(U2-NC{slash}FB-Pad4)") (class "Default")
      (node (ref "U2") (pin "4") (pinfunction "NC/FB_4") (pintype "passive"))
    )
    (net (code "71") (name "unconnected-(U3-(AIN0{slash}INT1)PD1-Pad7)") (class "Default")
      (node (ref "U3") (pin "7") (pinfunction "(AIN0/INT1)PD1_7") (pintype "bidirectional"))
    )
    (net (code "72") (name "unconnected-(U3-(AIN2{slash}PCINT11)PC2-Pad5)") (class "Default")
      (node (ref "U3") (pin "5") (pinfunction "(AIN2/PCINT11)PC2_5") (pintype "bidirectional"))
    )
    (net (code "73") (name "unconnected-(U3-(INT4{slash}ICP1{slash}CLK0)PC7-Pad22)") (class "Default")
      (node (ref "U3") (pin "22") (pinfunction "(INT4/ICP1/CLK0)PC7_22") (pintype "bidirectional"))
    )
    (net (code "74") (name "unconnected-(U3-(OC0B{slash}INT0)PD0-Pad6)") (class "Default")
      (node (ref "U3") (pin "6") (pinfunction "(OC0B/INT0)PD0_6") (pintype "bidirectional"))
    )
    (net (code "75") (name "unconnected-(U3-(OC1A{slash}PCINT8)PC6-Pad23)") (class "Default")
      (node (ref "U3") (pin "23") (pinfunction "(OC1A/PCINT8)PC6_23") (pintype "bidirectional"))
    )
    (net (code "76") (name "unconnected-(U3-(PCINT9{slash}OC1B)PC5-Pad25)") (class "Default")
      (node (ref "U3") (pin "25") (pinfunction "(PCINT9/OC1B)PC5_25") (pintype "bidirectional"))
    )
    (net (code "77") (name "unconnected-(U3-(PCINT10)PC4-Pad26)") (class "Default")
      (node (ref "U3") (pin "26") (pinfunction "(PCINT10)PC4_26") (pintype "bidirectional"))
    )
    (net (code "78") (name "unconnected-(U3-(RTS{slash}AIN5{slash}INT6)PD6-Pad12)") (class "Default")
      (node (ref "U3") (pin "12") (pinfunction "(RTS/AIN5/INT6)PD6_12") (pintype "bidirectional"))
    )
    (net (code "79") (name "unconnected-(U3-(SS{slash}PCINT0)PB0-Pad14)") (class "Default")
      (node (ref "U3") (pin "14") (pinfunction "(SS/PCINT0)PB0_14") (pintype "bidirectional"))
    )
  )
)
